# pdu_sval.net
KiCad netlist of a schematic drawn in EAGLE
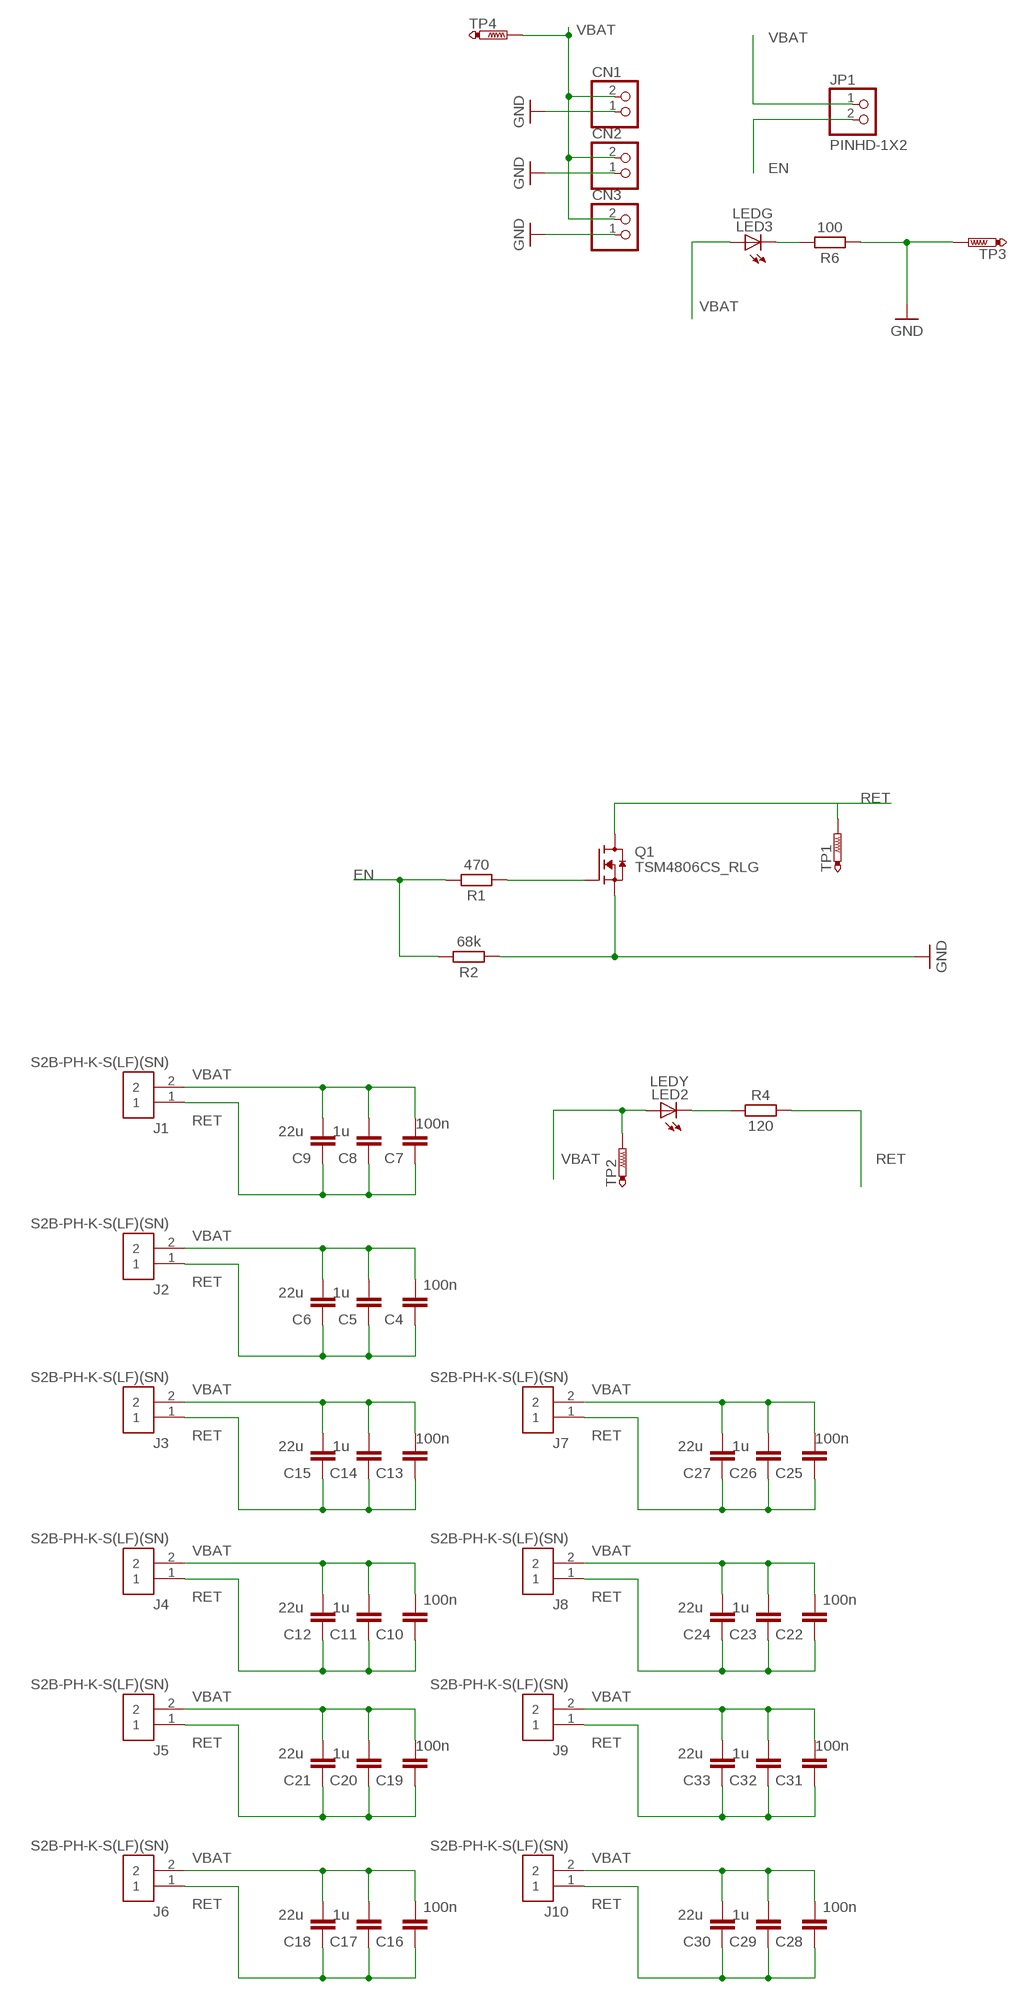
[diagram p0: schematic, sheet 1]

(export (version "E")
  (design (tool "Eeschema 10.0.6"))
  (components
    (comp (ref "C4")
      (value "100n")
      (footprint "eagle-import:CAPC1608X85")
      (libsource (lib "eagle-import") (part "CCHIP-0603(1608-METRIC)_"))
    )
    (comp (ref "C5")
      (value "1u")
      (footprint "eagle-import:CAPC1608X85")
      (libsource (lib "eagle-import") (part "CCHIP-0603(1608-METRIC)_"))
    )
    (comp (ref "C6")
      (value "22u")
      (footprint "eagle-import:CAPC1608X85")
      (libsource (lib "eagle-import") (part "CCHIP-0603(1608-METRIC)_"))
    )
    (comp (ref "C7")
      (value "100n")
      (footprint "eagle-import:CAPC1608X85")
      (libsource (lib "eagle-import") (part "CCHIP-0603(1608-METRIC)_"))
    )
    (comp (ref "C8")
      (value "1u")
      (footprint "eagle-import:CAPC1608X85")
      (libsource (lib "eagle-import") (part "CCHIP-0603(1608-METRIC)_"))
    )
    (comp (ref "C9")
      (value "22u")
      (footprint "eagle-import:CAPC1608X85")
      (libsource (lib "eagle-import") (part "CCHIP-0603(1608-METRIC)_"))
    )
    (comp (ref "C10")
      (value "100n")
      (footprint "eagle-import:CAPC1608X85")
      (libsource (lib "eagle-import") (part "CCHIP-0603(1608-METRIC)_"))
    )
    (comp (ref "C11")
      (value "1u")
      (footprint "eagle-import:CAPC1608X85")
      (libsource (lib "eagle-import") (part "CCHIP-0603(1608-METRIC)_"))
    )
    (comp (ref "C12")
      (value "22u")
      (footprint "eagle-import:CAPC1608X85")
      (libsource (lib "eagle-import") (part "CCHIP-0603(1608-METRIC)_"))
    )
    (comp (ref "C13")
      (value "100n")
      (footprint "eagle-import:CAPC1608X85")
      (libsource (lib "eagle-import") (part "CCHIP-0603(1608-METRIC)_"))
    )
    (comp (ref "C14")
      (value "1u")
      (footprint "eagle-import:CAPC1608X85")
      (libsource (lib "eagle-import") (part "CCHIP-0603(1608-METRIC)_"))
    )
    (comp (ref "C15")
      (value "22u")
      (footprint "eagle-import:CAPC1608X85")
      (libsource (lib "eagle-import") (part "CCHIP-0603(1608-METRIC)_"))
    )
    (comp (ref "C16")
      (value "100n")
      (footprint "eagle-import:CAPC1608X85")
      (libsource (lib "eagle-import") (part "CCHIP-0603(1608-METRIC)_"))
    )
    (comp (ref "C17")
      (value "1u")
      (footprint "eagle-import:CAPC1608X85")
      (libsource (lib "eagle-import") (part "CCHIP-0603(1608-METRIC)_"))
    )
    (comp (ref "C18")
      (value "22u")
      (footprint "eagle-import:CAPC1608X85")
      (libsource (lib "eagle-import") (part "CCHIP-0603(1608-METRIC)_"))
    )
    (comp (ref "C19")
      (value "100n")
      (footprint "eagle-import:CAPC1608X85")
      (libsource (lib "eagle-import") (part "CCHIP-0603(1608-METRIC)_"))
    )
    (comp (ref "C20")
      (value "1u")
      (footprint "eagle-import:CAPC1608X85")
      (libsource (lib "eagle-import") (part "CCHIP-0603(1608-METRIC)_"))
    )
    (comp (ref "C21")
      (value "22u")
      (footprint "eagle-import:CAPC1608X85")
      (libsource (lib "eagle-import") (part "CCHIP-0603(1608-METRIC)_"))
    )
    (comp (ref "C22")
      (value "100n")
      (footprint "eagle-import:CAPC1608X85")
      (libsource (lib "eagle-import") (part "CCHIP-0603(1608-METRIC)_"))
    )
    (comp (ref "C23")
      (value "1u")
      (footprint "eagle-import:CAPC1608X85")
      (libsource (lib "eagle-import") (part "CCHIP-0603(1608-METRIC)_"))
    )
    (comp (ref "C24")
      (value "22u")
      (footprint "eagle-import:CAPC1608X85")
      (libsource (lib "eagle-import") (part "CCHIP-0603(1608-METRIC)_"))
    )
    (comp (ref "C25")
      (value "100n")
      (footprint "eagle-import:CAPC1608X85")
      (libsource (lib "eagle-import") (part "CCHIP-0603(1608-METRIC)_"))
    )
    (comp (ref "C26")
      (value "1u")
      (footprint "eagle-import:CAPC1608X85")
      (libsource (lib "eagle-import") (part "CCHIP-0603(1608-METRIC)_"))
    )
    (comp (ref "C27")
      (value "22u")
      (footprint "eagle-import:CAPC1608X85")
      (libsource (lib "eagle-import") (part "CCHIP-0603(1608-METRIC)_"))
    )
    (comp (ref "C28")
      (value "100n")
      (footprint "eagle-import:CAPC1608X85")
      (libsource (lib "eagle-import") (part "CCHIP-0603(1608-METRIC)_"))
    )
    (comp (ref "C29")
      (value "1u")
      (footprint "eagle-import:CAPC1608X85")
      (libsource (lib "eagle-import") (part "CCHIP-0603(1608-METRIC)_"))
    )
    (comp (ref "C30")
      (value "22u")
      (footprint "eagle-import:CAPC1608X85")
      (libsource (lib "eagle-import") (part "CCHIP-0603(1608-METRIC)_"))
    )
    (comp (ref "C31")
      (value "100n")
      (footprint "eagle-import:CAPC1608X85")
      (libsource (lib "eagle-import") (part "CCHIP-0603(1608-METRIC)_"))
    )
    (comp (ref "C32")
      (value "1u")
      (footprint "eagle-import:CAPC1608X85")
      (libsource (lib "eagle-import") (part "CCHIP-0603(1608-METRIC)_"))
    )
    (comp (ref "C33")
      (value "22u")
      (footprint "eagle-import:CAPC1608X85")
      (libsource (lib "eagle-import") (part "CCHIP-0603(1608-METRIC)_"))
    )
    (comp (ref "CN1")
      (value "JST_2PIN-THM-RA")
      (footprint "eagle-import:JST-PH-2-THM-RA")
      (libsource (lib "eagle-import") (part "JST_2PIN-THM-RA"))
    )
    (comp (ref "CN2")
      (value "JST_2PIN-THM-RA")
      (footprint "eagle-import:JST-PH-2-THM-RA")
      (libsource (lib "eagle-import") (part "JST_2PIN-THM-RA"))
    )
    (comp (ref "CN3")
      (value "JST_2PIN-THM-RA")
      (footprint "eagle-import:JST-PH-2-THM-RA")
      (libsource (lib "eagle-import") (part "JST_2PIN-THM-RA"))
    )
    (comp (ref "J1")
      (value "S2B-PH-K-S(LF)(SN)")
      (footprint "eagle-import:S2B-PH-K-S(LF)(SN)")
      (fields
        (field (name "DIGI_KEY_PART_NUMBER") "455-1719-ND")
        (field (name "MANUFACTURER") "JST Sales America Inc.")
        (field (name "CREATED_BY") "PCBLayout.com")
      )
      (libsource (lib "eagle-import") (part "S2B-PH-K-S(LF)(SN)"))
    )
    (comp (ref "J2")
      (value "S2B-PH-K-S(LF)(SN)")
      (footprint "eagle-import:S2B-PH-K-S(LF)(SN)")
      (fields
        (field (name "DIGI_KEY_PART_NUMBER") "455-1719-ND")
        (field (name "MANUFACTURER") "JST Sales America Inc.")
        (field (name "CREATED_BY") "PCBLayout.com")
      )
      (libsource (lib "eagle-import") (part "S2B-PH-K-S(LF)(SN)"))
    )
    (comp (ref "J3")
      (value "S2B-PH-K-S(LF)(SN)")
      (footprint "eagle-import:S2B-PH-K-S(LF)(SN)")
      (fields
        (field (name "DIGI_KEY_PART_NUMBER") "455-1719-ND")
        (field (name "MANUFACTURER") "JST Sales America Inc.")
        (field (name "CREATED_BY") "PCBLayout.com")
      )
      (libsource (lib "eagle-import") (part "S2B-PH-K-S(LF)(SN)"))
    )
    (comp (ref "J4")
      (value "S2B-PH-K-S(LF)(SN)")
      (footprint "eagle-import:S2B-PH-K-S(LF)(SN)")
      (fields
        (field (name "DIGI_KEY_PART_NUMBER") "455-1719-ND")
        (field (name "MANUFACTURER") "JST Sales America Inc.")
        (field (name "CREATED_BY") "PCBLayout.com")
      )
      (libsource (lib "eagle-import") (part "S2B-PH-K-S(LF)(SN)"))
    )
    (comp (ref "J5")
      (value "S2B-PH-K-S(LF)(SN)")
      (footprint "eagle-import:S2B-PH-K-S(LF)(SN)")
      (fields
        (field (name "DIGI_KEY_PART_NUMBER") "455-1719-ND")
        (field (name "MANUFACTURER") "JST Sales America Inc.")
        (field (name "CREATED_BY") "PCBLayout.com")
      )
      (libsource (lib "eagle-import") (part "S2B-PH-K-S(LF)(SN)"))
    )
    (comp (ref "J6")
      (value "S2B-PH-K-S(LF)(SN)")
      (footprint "eagle-import:S2B-PH-K-S(LF)(SN)")
      (fields
        (field (name "DIGI_KEY_PART_NUMBER") "455-1719-ND")
        (field (name "MANUFACTURER") "JST Sales America Inc.")
        (field (name "CREATED_BY") "PCBLayout.com")
      )
      (libsource (lib "eagle-import") (part "S2B-PH-K-S(LF)(SN)"))
    )
    (comp (ref "J7")
      (value "S2B-PH-K-S(LF)(SN)")
      (footprint "eagle-import:S2B-PH-K-S(LF)(SN)")
      (fields
        (field (name "DIGI_KEY_PART_NUMBER") "455-1719-ND")
        (field (name "MANUFACTURER") "JST Sales America Inc.")
        (field (name "CREATED_BY") "PCBLayout.com")
      )
      (libsource (lib "eagle-import") (part "S2B-PH-K-S(LF)(SN)"))
    )
    (comp (ref "J8")
      (value "S2B-PH-K-S(LF)(SN)")
      (footprint "eagle-import:S2B-PH-K-S(LF)(SN)")
      (fields
        (field (name "DIGI_KEY_PART_NUMBER") "455-1719-ND")
        (field (name "MANUFACTURER") "JST Sales America Inc.")
        (field (name "CREATED_BY") "PCBLayout.com")
      )
      (libsource (lib "eagle-import") (part "S2B-PH-K-S(LF)(SN)"))
    )
    (comp (ref "J9")
      (value "S2B-PH-K-S(LF)(SN)")
      (footprint "eagle-import:S2B-PH-K-S(LF)(SN)")
      (fields
        (field (name "DIGI_KEY_PART_NUMBER") "455-1719-ND")
        (field (name "MANUFACTURER") "JST Sales America Inc.")
        (field (name "CREATED_BY") "PCBLayout.com")
      )
      (libsource (lib "eagle-import") (part "S2B-PH-K-S(LF)(SN)"))
    )
    (comp (ref "J10")
      (value "S2B-PH-K-S(LF)(SN)")
      (footprint "eagle-import:S2B-PH-K-S(LF)(SN)")
      (fields
        (field (name "DIGI_KEY_PART_NUMBER") "455-1719-ND")
        (field (name "MANUFACTURER") "JST Sales America Inc.")
        (field (name "CREATED_BY") "PCBLayout.com")
      )
      (libsource (lib "eagle-import") (part "S2B-PH-K-S(LF)(SN)"))
    )
    (comp (ref "JP1")
      (value "PINHD-1X2")
      (footprint "eagle-import:1X02")
      (fields (field (name "MANUFACTURER") "Generic"))
      (libsource (lib "eagle-import") (part "PINHD-1X2"))
    )
    (comp (ref "LED2")
      (value "LEDY")
      (footprint "eagle-import:CHIPLED_0805")
      (libsource (lib "eagle-import") (part "LEDCHIPLED_0805"))
    )
    (comp (ref "LED3")
      (value "LEDG")
      (footprint "eagle-import:CHIPLED_0805")
      (libsource (lib "eagle-import") (part "LEDCHIPLED_0805"))
    )
    (comp (ref "Q1")
      (value "TSM4806CS_RLG")
      (footprint "eagle-import:SOP127P600X200-8N")
      (fields (field (name "MANUFACTURER") "Taiwan Semiconductor"))
      (libsource (lib "eagle-import") (part "TSM4806CS_RLG"))
    )
    (comp (ref "R1")
      (value "470")
      (footprint "eagle-import:RESC1608X60")
      (libsource (lib "eagle-import") (part "RCHIP-0603(1608-METRIC)_"))
    )
    (comp (ref "R2")
      (value "68k")
      (footprint "eagle-import:RESC1608X60")
      (libsource (lib "eagle-import") (part "RCHIP-0603(1608-METRIC)_"))
    )
    (comp (ref "R4")
      (value "120")
      (footprint "eagle-import:RESC1608X60")
      (libsource (lib "eagle-import") (part "RCHIP-0603(1608-METRIC)_"))
    )
    (comp (ref "R6")
      (value "100")
      (footprint "eagle-import:RESC1608X60")
      (libsource (lib "eagle-import") (part "RCHIP-0603(1608-METRIC)_"))
    )
    (comp (ref "TP1")
      (value "PTR1PAD1-13")
      (footprint "eagle-import:P1-13")
      (libsource (lib "eagle-import") (part "PTR1PAD1-13"))
    )
    (comp (ref "TP2")
      (value "PTR1PAD1-13")
      (footprint "eagle-import:P1-13")
      (libsource (lib "eagle-import") (part "PTR1PAD1-13"))
    )
    (comp (ref "TP3")
      (value "PTR1PAD1-13")
      (footprint "eagle-import:P1-13")
      (libsource (lib "eagle-import") (part "PTR1PAD1-13"))
    )
    (comp (ref "TP4")
      (value "PTR1PAD1-13")
      (footprint "eagle-import:P1-13")
      (libsource (lib "eagle-import") (part "PTR1PAD1-13"))
    )
  )
  (nets
    (net (code "1") (name "/EN") (class "Default")
      (node (ref "JP1") (pin "2") (pinfunction "2_2") (pintype "passive"))
      (node (ref "R1") (pin "2") (pinfunction "2_2") (pintype "passive"))
      (node (ref "R2") (pin "2") (pinfunction "2_2") (pintype "passive"))
    )
    (net (code "2") (name "/RET") (class "Default")
      (node (ref "C10") (pin "1") (pinfunction "1_1") (pintype "passive"))
      (node (ref "C11") (pin "1") (pinfunction "1_1") (pintype "passive"))
      (node (ref "C12") (pin "1") (pinfunction "1_1") (pintype "passive"))
      (node (ref "C13") (pin "1") (pinfunction "1_1") (pintype "passive"))
      (node (ref "C14") (pin "1") (pinfunction "1_1") (pintype "passive"))
      (node (ref "C15") (pin "1") (pinfunction "1_1") (pintype "passive"))
      (node (ref "C16") (pin "1") (pinfunction "1_1") (pintype "passive"))
      (node (ref "C17") (pin "1") (pinfunction "1_1") (pintype "passive"))
      (node (ref "C18") (pin "1") (pinfunction "1_1") (pintype "passive"))
      (node (ref "C19") (pin "1") (pinfunction "1_1") (pintype "passive"))
      (node (ref "C20") (pin "1") (pinfunction "1_1") (pintype "passive"))
      (node (ref "C21") (pin "1") (pinfunction "1_1") (pintype "passive"))
      (node (ref "C22") (pin "1") (pinfunction "1_1") (pintype "passive"))
      (node (ref "C23") (pin "1") (pinfunction "1_1") (pintype "passive"))
      (node (ref "C24") (pin "1") (pinfunction "1_1") (pintype "passive"))
      (node (ref "C25") (pin "1") (pinfunction "1_1") (pintype "passive"))
      (node (ref "C26") (pin "1") (pinfunction "1_1") (pintype "passive"))
      (node (ref "C27") (pin "1") (pinfunction "1_1") (pintype "passive"))
      (node (ref "C28") (pin "1") (pinfunction "1_1") (pintype "passive"))
      (node (ref "C29") (pin "1") (pinfunction "1_1") (pintype "passive"))
      (node (ref "C30") (pin "1") (pinfunction "1_1") (pintype "passive"))
      (node (ref "C31") (pin "1") (pinfunction "1_1") (pintype "passive"))
      (node (ref "C32") (pin "1") (pinfunction "1_1") (pintype "passive"))
      (node (ref "C33") (pin "1") (pinfunction "1_1") (pintype "passive"))
      (node (ref "C4") (pin "1") (pinfunction "1_1") (pintype "passive"))
      (node (ref "C5") (pin "1") (pinfunction "1_1") (pintype "passive"))
      (node (ref "C6") (pin "1") (pinfunction "1_1") (pintype "passive"))
      (node (ref "C7") (pin "1") (pinfunction "1_1") (pintype "passive"))
      (node (ref "C8") (pin "1") (pinfunction "1_1") (pintype "passive"))
      (node (ref "C9") (pin "1") (pinfunction "1_1") (pintype "passive"))
      (node (ref "J1") (pin "1") (pinfunction "1_1") (pintype "passive"))
      (node (ref "J10") (pin "1") (pinfunction "1_1") (pintype "passive"))
      (node (ref "J2") (pin "1") (pinfunction "1_1") (pintype "passive"))
      (node (ref "J3") (pin "1") (pinfunction "1_1") (pintype "passive"))
      (node (ref "J4") (pin "1") (pinfunction "1_1") (pintype "passive"))
      (node (ref "J5") (pin "1") (pinfunction "1_1") (pintype "passive"))
      (node (ref "J6") (pin "1") (pinfunction "1_1") (pintype "passive"))
      (node (ref "J7") (pin "1") (pinfunction "1_1") (pintype "passive"))
      (node (ref "J8") (pin "1") (pinfunction "1_1") (pintype "passive"))
      (node (ref "J9") (pin "1") (pinfunction "1_1") (pintype "passive"))
      (node (ref "Q1") (pin "5") (pinfunction "D_5") (pintype "passive"))
      (node (ref "Q1") (pin "6") (pinfunction "D_6") (pintype "passive"))
      (node (ref "Q1") (pin "7") (pinfunction "D_7") (pintype "passive"))
      (node (ref "Q1") (pin "8") (pinfunction "D_8") (pintype "passive"))
      (node (ref "R4") (pin "2") (pinfunction "2_2") (pintype "passive"))
      (node (ref "TP1") (pin "TP") (pinfunction "TP_TP") (pintype "input"))
    )
    (net (code "3") (name "/VBAT") (class "Default")
      (node (ref "C10") (pin "2") (pinfunction "2_2") (pintype "passive"))
      (node (ref "C11") (pin "2") (pinfunction "2_2") (pintype "passive"))
      (node (ref "C12") (pin "2") (pinfunction "2_2") (pintype "passive"))
      (node (ref "C13") (pin "2") (pinfunction "2_2") (pintype "passive"))
      (node (ref "C14") (pin "2") (pinfunction "2_2") (pintype "passive"))
      (node (ref "C15") (pin "2") (pinfunction "2_2") (pintype "passive"))
      (node (ref "C16") (pin "2") (pinfunction "2_2") (pintype "passive"))
      (node (ref "C17") (pin "2") (pinfunction "2_2") (pintype "passive"))
      (node (ref "C18") (pin "2") (pinfunction "2_2") (pintype "passive"))
      (node (ref "C19") (pin "2") (pinfunction "2_2") (pintype "passive"))
      (node (ref "C20") (pin "2") (pinfunction "2_2") (pintype "passive"))
      (node (ref "C21") (pin "2") (pinfunction "2_2") (pintype "passive"))
      (node (ref "C22") (pin "2") (pinfunction "2_2") (pintype "passive"))
      (node (ref "C23") (pin "2") (pinfunction "2_2") (pintype "passive"))
      (node (ref "C24") (pin "2") (pinfunction "2_2") (pintype "passive"))
      (node (ref "C25") (pin "2") (pinfunction "2_2") (pintype "passive"))
      (node (ref "C26") (pin "2") (pinfunction "2_2") (pintype "passive"))
      (node (ref "C27") (pin "2") (pinfunction "2_2") (pintype "passive"))
      (node (ref "C28") (pin "2") (pinfunction "2_2") (pintype "passive"))
      (node (ref "C29") (pin "2") (pinfunction "2_2") (pintype "passive"))
      (node (ref "C30") (pin "2") (pinfunction "2_2") (pintype "passive"))
      (node (ref "C31") (pin "2") (pinfunction "2_2") (pintype "passive"))
      (node (ref "C32") (pin "2") (pinfunction "2_2") (pintype "passive"))
      (node (ref "C33") (pin "2") (pinfunction "2_2") (pintype "passive"))
      (node (ref "C4") (pin "2") (pinfunction "2_2") (pintype "passive"))
      (node (ref "C5") (pin "2") (pinfunction "2_2") (pintype "passive"))
      (node (ref "C6") (pin "2") (pinfunction "2_2") (pintype "passive"))
      (node (ref "C7") (pin "2") (pinfunction "2_2") (pintype "passive"))
      (node (ref "C8") (pin "2") (pinfunction "2_2") (pintype "passive"))
      (node (ref "C9") (pin "2") (pinfunction "2_2") (pintype "passive"))
      (node (ref "CN1") (pin "2") (pinfunction "1_2") (pintype "passive"))
      (node (ref "CN2") (pin "2") (pinfunction "1_2") (pintype "passive"))
      (node (ref "CN3") (pin "2") (pinfunction "1_2") (pintype "passive"))
      (node (ref "J1") (pin "2") (pinfunction "2_2") (pintype "passive"))
      (node (ref "J10") (pin "2") (pinfunction "2_2") (pintype "passive"))
      (node (ref "J2") (pin "2") (pinfunction "2_2") (pintype "passive"))
      (node (ref "J3") (pin "2") (pinfunction "2_2") (pintype "passive"))
      (node (ref "J4") (pin "2") (pinfunction "2_2") (pintype "passive"))
      (node (ref "J5") (pin "2") (pinfunction "2_2") (pintype "passive"))
      (node (ref "J6") (pin "2") (pinfunction "2_2") (pintype "passive"))
      (node (ref "J7") (pin "2") (pinfunction "2_2") (pintype "passive"))
      (node (ref "J8") (pin "2") (pinfunction "2_2") (pintype "passive"))
      (node (ref "J9") (pin "2") (pinfunction "2_2") (pintype "passive"))
      (node (ref "JP1") (pin "1") (pinfunction "1_1") (pintype "passive"))
      (node (ref "LED2") (pin "A") (pinfunction "A_A") (pintype "passive"))
      (node (ref "LED3") (pin "A") (pinfunction "A_A") (pintype "passive"))
      (node (ref "TP2") (pin "TP") (pinfunction "TP_TP") (pintype "input"))
      (node (ref "TP4") (pin "TP") (pinfunction "TP_TP") (pintype "input"))
    )
    (net (code "4") (name "GND") (class "Default")
      (node (ref "CN1") (pin "1") (pinfunction "2_1") (pintype "passive"))
      (node (ref "CN2") (pin "1") (pinfunction "2_1") (pintype "passive"))
      (node (ref "CN3") (pin "1") (pinfunction "2_1") (pintype "passive"))
      (node (ref "Q1") (pin "1") (pinfunction "S_1") (pintype "passive"))
      (node (ref "Q1") (pin "2") (pinfunction "S_2") (pintype "passive"))
      (node (ref "Q1") (pin "3") (pinfunction "S_3") (pintype "passive"))
      (node (ref "R2") (pin "1") (pinfunction "1_1") (pintype "passive"))
      (node (ref "R6") (pin "1") (pinfunction "1_1") (pintype "passive"))
      (node (ref "TP3") (pin "TP") (pinfunction "TP_TP") (pintype "input"))
    )
    (net (code "5") (name "Net-(LED2-PadC)") (class "Default")
      (node (ref "LED2") (pin "C") (pinfunction "C_C") (pintype "passive"))
      (node (ref "R4") (pin "1") (pinfunction "1_1") (pintype "passive"))
    )
    (net (code "6") (name "Net-(LED3-PadC)") (class "Default")
      (node (ref "LED3") (pin "C") (pinfunction "C_C") (pintype "passive"))
      (node (ref "R6") (pin "2") (pinfunction "2_2") (pintype "passive"))
    )
    (net (code "7") (name "Net-(Q1-G)") (class "Default")
      (node (ref "Q1") (pin "4") (pinfunction "G_4") (pintype "passive"))
      (node (ref "R1") (pin "1") (pinfunction "1_1") (pintype "passive"))
    )
  )
)
